# light_detector.net
KiCad netlist of a schematic drawn in EAGLE
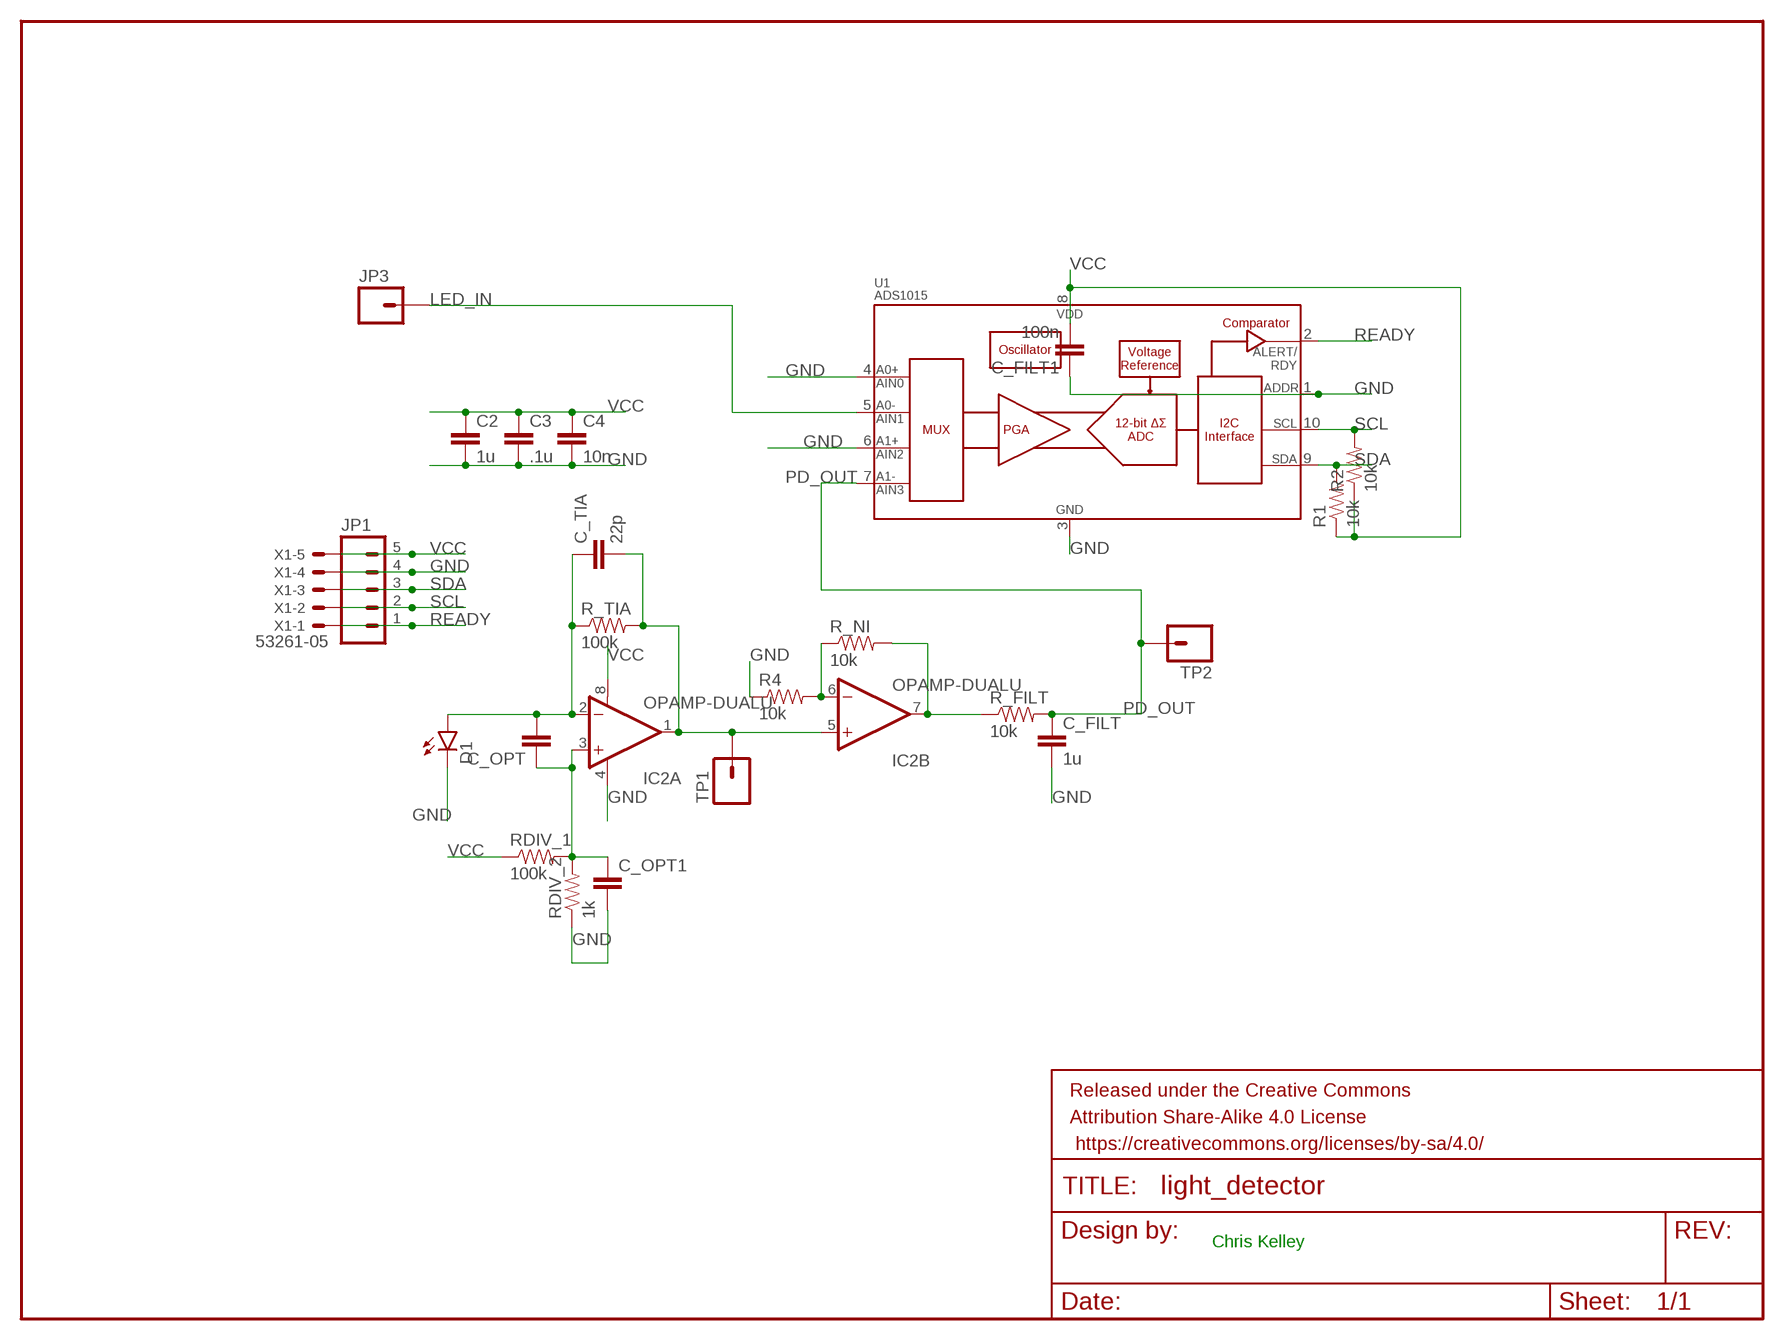
[diagram p0: schematic, sheet 1]

(export (version "E")
  (design (tool "Eeschema 10.0.6"))
  (components
    (comp (ref "C2")
      (value "1u")
      (footprint "eagle-import:0805")
      (libsource (lib "eagle-import") (part "CAP0805"))
    )
    (comp (ref "C3")
      (value ".1u")
      (footprint "eagle-import:0805")
      (libsource (lib "eagle-import") (part "CAP0805"))
    )
    (comp (ref "C4")
      (value "10n")
      (footprint "eagle-import:0805")
      (libsource (lib "eagle-import") (part "CAP0805"))
    )
    (comp (ref "C_FILT")
      (value "1u")
      (footprint "eagle-import:0805")
      (libsource (lib "eagle-import") (part "CAP0805"))
    )
    (comp (ref "C_FILT1")
      (value "100n")
      (footprint "eagle-import:0805")
      (libsource (lib "eagle-import") (part "CAP0805"))
    )
    (comp (ref "C_OPT")
      (value "CAP0805")
      (footprint "eagle-import:0805")
      (libsource (lib "eagle-import") (part "CAP0805"))
    )
    (comp (ref "C_OPT1")
      (value "CAP0805")
      (footprint "eagle-import:0805")
      (libsource (lib "eagle-import") (part "CAP0805"))
    )
    (comp (ref "C_TIA")
      (value "22p")
      (footprint "eagle-import:0805")
      (libsource (lib "eagle-import") (part "CAP0805"))
    )
    (comp (ref "D1")
      (value "LED5MM")
      (footprint "eagle-import:LED5MM")
      (libsource (lib "eagle-import") (part "LED5MM"))
    )
    (comp (ref "FRAME1")
      (value "FRAME-LETTER")
      (footprint "eagle-import:CREATIVE_COMMONS")
      (libsource (lib "eagle-import") (part "FRAME-LETTER"))
    )
    (comp (ref "IC2")
      (value "OPAMP-DUALU")
      (footprint "eagle-import:SO08")
      (libsource (lib "eagle-import") (part "OPAMP-DUALU"))
    )
    (comp (ref "JP1")
      (value "M05PTH")
      (footprint "eagle-import:1X05")
      (libsource (lib "eagle-import") (part "M05PTH"))
    )
    (comp (ref "JP3")
      (value "M01PTH")
      (footprint "eagle-import:1X01")
      (libsource (lib "eagle-import") (part "M01PTH"))
    )
    (comp (ref "R1")
      (value "10k")
      (footprint "eagle-import:0603-RES")
      (libsource (lib "eagle-import") (part "RESISTOR0603-RES"))
    )
    (comp (ref "R2")
      (value "10k")
      (footprint "eagle-import:0603-RES")
      (libsource (lib "eagle-import") (part "RESISTOR0603-RES"))
    )
    (comp (ref "R4")
      (value "10k")
      (footprint "eagle-import:0603-RES")
      (libsource (lib "eagle-import") (part "RESISTOR0603-RES"))
    )
    (comp (ref "RDIV_1")
      (value "100k")
      (footprint "eagle-import:0603-RES")
      (libsource (lib "eagle-import") (part "RESISTOR0603-RES"))
    )
    (comp (ref "RDIV_2")
      (value "1k")
      (footprint "eagle-import:0603-RES")
      (libsource (lib "eagle-import") (part "RESISTOR0603-RES"))
    )
    (comp (ref "R_FILT")
      (value "10k")
      (footprint "eagle-import:0603-RES")
      (libsource (lib "eagle-import") (part "RESISTOR0603-RES"))
    )
    (comp (ref "R_NI")
      (value "10k")
      (footprint "eagle-import:0603-RES")
      (libsource (lib "eagle-import") (part "RESISTOR0603-RES"))
    )
    (comp (ref "R_TIA")
      (value "100k")
      (footprint "eagle-import:0603-RES")
      (libsource (lib "eagle-import") (part "RESISTOR0603-RES"))
    )
    (comp (ref "TP1")
      (value "M01PTH")
      (footprint "eagle-import:1X01")
      (libsource (lib "eagle-import") (part "M01PTH"))
    )
    (comp (ref "TP2")
      (value "M01PTH")
      (footprint "eagle-import:1X01")
      (libsource (lib "eagle-import") (part "M01PTH"))
    )
    (comp (ref "U1")
      (value "ADS1015")
      (footprint "eagle-import:MSOP10")
      (libsource (lib "eagle-import") (part "ADS1015"))
    )
    (comp (ref "X1")
      (value "53261-05")
      (footprint "eagle-import:53261-05")
      (libsource (lib "eagle-import") (part "53?-05261"))
    )
  )
  (nets
    (net (code "1") (name "/GND") (class "Default")
      (node (ref "C2") (pin "2") (pinfunction "2_2") (pintype "passive"))
      (node (ref "C3") (pin "2") (pinfunction "2_2") (pintype "passive"))
      (node (ref "C4") (pin "2") (pinfunction "2_2") (pintype "passive"))
      (node (ref "C_FILT") (pin "2") (pinfunction "2_2") (pintype "passive"))
      (node (ref "C_FILT1") (pin "1") (pinfunction "1_1") (pintype "passive"))
      (node (ref "C_OPT1") (pin "2") (pinfunction "2_2") (pintype "passive"))
      (node (ref "D1") (pin "K") (pinfunction "C_K") (pintype "passive"))
      (node (ref "IC2") (pin "4") (pinfunction "V-_4") (pintype "power_in"))
      (node (ref "JP1") (pin "4") (pinfunction "4_4") (pintype "passive"))
      (node (ref "R4") (pin "1") (pinfunction "1_1") (pintype "passive"))
      (node (ref "RDIV_2") (pin "1") (pinfunction "1_1") (pintype "passive"))
      (node (ref "U1") (pin "1") (pinfunction "ADDR_1") (pintype "bidirectional"))
      (node (ref "U1") (pin "3") (pinfunction "VSS_3") (pintype "bidirectional"))
      (node (ref "U1") (pin "4") (pinfunction "AIN0_4") (pintype "bidirectional"))
      (node (ref "U1") (pin "6") (pinfunction "AIN2_6") (pintype "bidirectional"))
      (node (ref "X1") (pin "4") (pinfunction "S_4") (pintype "passive"))
    )
    (net (code "2") (name "/LED_IN") (class "Default")
      (node (ref "JP3") (pin "1") (pinfunction "1_1") (pintype "passive"))
      (node (ref "U1") (pin "5") (pinfunction "AIN1_5") (pintype "bidirectional"))
    )
    (net (code "3") (name "/PD_OUT") (class "Default")
      (node (ref "C_FILT") (pin "1") (pinfunction "1_1") (pintype "passive"))
      (node (ref "R_FILT") (pin "2") (pinfunction "2_2") (pintype "passive"))
      (node (ref "TP2") (pin "1") (pinfunction "1_1") (pintype "passive"))
      (node (ref "U1") (pin "7") (pinfunction "AIN3_7") (pintype "bidirectional"))
    )
    (net (code "4") (name "/READY") (class "Default")
      (node (ref "JP1") (pin "1") (pinfunction "1_1") (pintype "passive"))
      (node (ref "U1") (pin "2") (pinfunction "ALERT/RDY_2") (pintype "bidirectional"))
      (node (ref "X1") (pin "1") (pinfunction "S_1") (pintype "passive"))
    )
    (net (code "5") (name "/SCL") (class "Default")
      (node (ref "JP1") (pin "2") (pinfunction "2_2") (pintype "passive"))
      (node (ref "R2") (pin "2") (pinfunction "2_2") (pintype "passive"))
      (node (ref "U1") (pin "10") (pinfunction "SCL_10") (pintype "bidirectional"))
      (node (ref "X1") (pin "2") (pinfunction "S_2") (pintype "passive"))
    )
    (net (code "6") (name "/SDA") (class "Default")
      (node (ref "JP1") (pin "3") (pinfunction "3_3") (pintype "passive"))
      (node (ref "R1") (pin "2") (pinfunction "2_2") (pintype "passive"))
      (node (ref "U1") (pin "9") (pinfunction "SDA_9") (pintype "bidirectional"))
      (node (ref "X1") (pin "3") (pinfunction "S_3") (pintype "passive"))
    )
    (net (code "7") (name "/VCC") (class "Default")
      (node (ref "C2") (pin "1") (pinfunction "1_1") (pintype "passive"))
      (node (ref "C3") (pin "1") (pinfunction "1_1") (pintype "passive"))
      (node (ref "C4") (pin "1") (pinfunction "1_1") (pintype "passive"))
      (node (ref "C_FILT1") (pin "2") (pinfunction "2_2") (pintype "passive"))
      (node (ref "IC2") (pin "8") (pinfunction "V+_8") (pintype "power_in"))
      (node (ref "JP1") (pin "5") (pinfunction "5_5") (pintype "passive"))
      (node (ref "R1") (pin "1") (pinfunction "1_1") (pintype "passive"))
      (node (ref "R2") (pin "1") (pinfunction "1_1") (pintype "passive"))
      (node (ref "RDIV_1") (pin "1") (pinfunction "1_1") (pintype "passive"))
      (node (ref "U1") (pin "8") (pinfunction "VDD_8") (pintype "bidirectional"))
      (node (ref "X1") (pin "5") (pinfunction "S_5") (pintype "passive"))
    )
    (net (code "8") (name "Net-(IC2A-+IN)") (class "Default")
      (node (ref "C_OPT") (pin "1") (pinfunction "1_1") (pintype "passive"))
      (node (ref "C_OPT1") (pin "1") (pinfunction "1_1") (pintype "passive"))
      (node (ref "IC2") (pin "3") (pinfunction "+IN_3") (pintype "input"))
      (node (ref "RDIV_1") (pin "2") (pinfunction "2_2") (pintype "passive"))
      (node (ref "RDIV_2") (pin "2") (pinfunction "2_2") (pintype "passive"))
    )
    (net (code "9") (name "Net-(IC2A--IN)") (class "Default")
      (node (ref "C_OPT") (pin "2") (pinfunction "2_2") (pintype "passive"))
      (node (ref "C_TIA") (pin "1") (pinfunction "1_1") (pintype "passive"))
      (node (ref "D1") (pin "A") (pinfunction "A_A") (pintype "passive"))
      (node (ref "IC2") (pin "2") (pinfunction "-IN_2") (pintype "input"))
      (node (ref "R_TIA") (pin "1") (pinfunction "1_1") (pintype "passive"))
    )
    (net (code "10") (name "Net-(IC2A-OUT)") (class "Default")
      (node (ref "C_TIA") (pin "2") (pinfunction "2_2") (pintype "passive"))
      (node (ref "IC2") (pin "1") (pinfunction "OUT_1") (pintype "output"))
      (node (ref "IC2") (pin "5") (pinfunction "+IN_5") (pintype "input"))
      (node (ref "R_TIA") (pin "2") (pinfunction "2_2") (pintype "passive"))
      (node (ref "TP1") (pin "1") (pinfunction "1_1") (pintype "passive"))
    )
    (net (code "11") (name "Net-(IC2B--IN)") (class "Default")
      (node (ref "IC2") (pin "6") (pinfunction "-IN_6") (pintype "input"))
      (node (ref "R4") (pin "2") (pinfunction "2_2") (pintype "passive"))
      (node (ref "R_NI") (pin "1") (pinfunction "1_1") (pintype "passive"))
    )
    (net (code "12") (name "Net-(IC2B-OUT)") (class "Default")
      (node (ref "IC2") (pin "7") (pinfunction "OUT_7") (pintype "output"))
      (node (ref "R_FILT") (pin "1") (pinfunction "1_1") (pintype "passive"))
      (node (ref "R_NI") (pin "2") (pinfunction "2_2") (pintype "passive"))
    )
  )
)
